# AD8232.net
KiCad netlist of a schematic drawn in Altium Designer
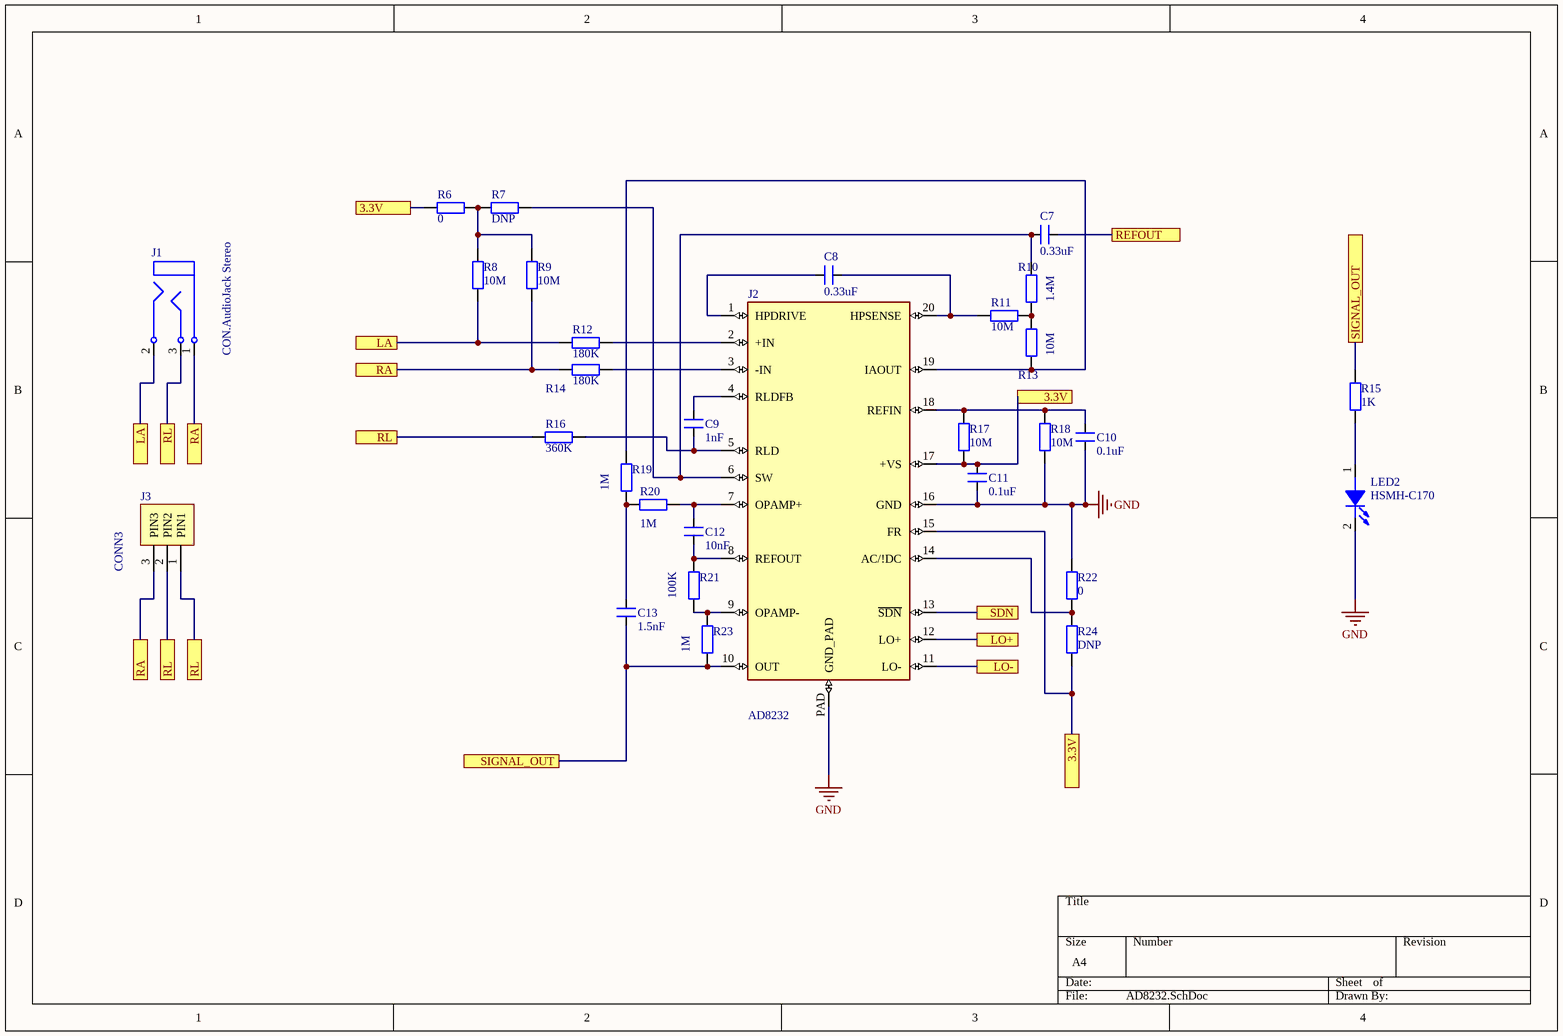
[diagram p0: AD8232.SchDoc]

(export (version "E")
  (design (tool "Eeschema 10.0.6"))
  (components
    (comp (ref "C7")
      (value "0.33uF")
      (footprint "SM-0805")
      (description "Cap SMD")
      (libsource (lib "hphonglib") (part "CM"))
    )
    (comp (ref "C8")
      (value "0.33uF")
      (footprint "SM-0805")
      (description "Cap SMD")
      (libsource (lib "hphonglib") (part "CM"))
    )
    (comp (ref "C9")
      (value "1nF")
      (footprint "SM-0805")
      (description "Cap SMD")
      (libsource (lib "hphonglib") (part "CM"))
    )
    (comp (ref "C10")
      (value "0.1uF")
      (footprint "SM-0805")
      (description "Cap SMD")
      (libsource (lib "hphonglib") (part "CM"))
    )
    (comp (ref "C11")
      (value "0.1uF")
      (footprint "SM-0805")
      (description "Cap SMD")
      (libsource (lib "hphonglib") (part "CM"))
    )
    (comp (ref "C12")
      (value "10nF")
      (footprint "SM-0805")
      (description "Cap SMD")
      (libsource (lib "hphonglib") (part "CM"))
    )
    (comp (ref "C13")
      (value "1.5nF")
      (footprint "SM-0805")
      (description "Cap SMD")
      (libsource (lib "hphonglib") (part "CM"))
    )
    (comp (ref "J1")
      (value "CON.AudioJack Stereo")
      (footprint "SJ-3523-SMT")
      (description "AUDIO JACK 3.5MM STEREO SMD")
      (fields (field (name "PUBLISHER") "Altium Limited"))
      (libsource (lib "hphonglib") (part "CON.AudioJack Stereo"))
    )
    (comp (ref "J2")
      (value "AD8232")
      (footprint "AD8232")
      (description "ECG Front End 20-LFCSP-WQ (4x4)")
      (fields (field (name "MF") "Analog Devices"))
      (libsource (lib "ECG_Taller_2021") (part "AD8232"))
    )
    (comp (ref "J3")
      (value "CONN3")
      (footprint "CONN3")
      (libsource (lib "Schlib-PCB-Invernadero") (part "Bornera_3_pin"))
    )
    (comp (ref "LED2")
      (value "HSMH-C170")
      (footprint "LED.SMD.RED")
      (description "Typical GaAs SMD LED")
      (fields (field (name "MANUFACTURER") "Lite-On Inc") (field (name "PUBLISHER") "Hoang Nguyen"))
      (libsource (lib "hphonglib") (part "LED_1"))
    )
    (comp (ref "R6")
      (value "0")
      (footprint "DIEN TRO 0805")
      (description "RES_0805")
      (fields (field (name "Comment") "RES_SMD_0805") (field (name "PUBLISHER") "Altium Limited"))
      (libsource (lib "") (part "RES_SMD_0805_1"))
    )
    (comp (ref "R7")
      (value "DNP")
      (footprint "DIEN TRO 0805")
      (description "RES_0805")
      (fields (field (name "Comment") "RES_SMD_0805") (field (name "PUBLISHER") "Altium Limited"))
      (libsource (lib "") (part "RES_SMD_0805_1"))
    )
    (comp (ref "R8")
      (value "10M")
      (footprint "DIEN TRO 0805")
      (description "RES_0805")
      (fields (field (name "Comment") "RES_SMD_0805") (field (name "PUBLISHER") "Altium Limited"))
      (libsource (lib "hphonglib") (part "RES_SMD_0805"))
    )
    (comp (ref "R9")
      (value "10M")
      (footprint "DIEN TRO 0805")
      (description "RES_0805")
      (fields (field (name "Comment") "RES_SMD_0805") (field (name "PUBLISHER") "Altium Limited"))
      (libsource (lib "hphonglib") (part "RES_SMD_0805"))
    )
    (comp (ref "R10")
      (value "1.4M")
      (footprint "DIEN TRO 0805")
      (description "RES_0805")
      (fields (field (name "Comment") "RES_SMD_0805") (field (name "PUBLISHER") "Altium Limited"))
      (libsource (lib "hphonglib") (part "RES_SMD_0805"))
    )
    (comp (ref "R11")
      (value "10M")
      (footprint "DIEN TRO 0805")
      (description "RES_0805")
      (fields (field (name "Comment") "RES_SMD_0805") (field (name "PUBLISHER") "Altium Limited"))
      (libsource (lib "") (part "RES_SMD_0805_1"))
    )
    (comp (ref "R12")
      (value "180K")
      (footprint "DIEN TRO 0805")
      (description "RES_0805")
      (fields (field (name "Comment") "RES_SMD_0805") (field (name "PUBLISHER") "Altium Limited"))
      (libsource (lib "") (part "RES_SMD_0805_1"))
    )
    (comp (ref "R13")
      (value "10M")
      (footprint "DIEN TRO 0805")
      (description "RES_0805")
      (fields (field (name "Comment") "RES_SMD_0805") (field (name "PUBLISHER") "Altium Limited"))
      (libsource (lib "hphonglib") (part "RES_SMD_0805"))
    )
    (comp (ref "R14")
      (value "180K")
      (footprint "DIEN TRO 0805")
      (description "RES_0805")
      (fields (field (name "Comment") "RES_SMD_0805") (field (name "PUBLISHER") "Altium Limited"))
      (libsource (lib "") (part "RES_SMD_0805_1"))
    )
    (comp (ref "R15")
      (value "1K")
      (footprint "DIEN TRO 0805")
      (description "RES_0805")
      (fields (field (name "Comment") "RES_SMD_0805") (field (name "PUBLISHER") "Altium Limited"))
      (libsource (lib "") (part "RES_SMD_0805_2"))
    )
    (comp (ref "R16")
      (value "360K")
      (footprint "DIEN TRO 0805")
      (description "RES_0805")
      (fields (field (name "Comment") "RES_SMD_0805") (field (name "PUBLISHER") "Altium Limited"))
      (libsource (lib "") (part "RES_SMD_0805_1"))
    )
    (comp (ref "R17")
      (value "10M")
      (footprint "DIEN TRO 0805")
      (description "RES_0805")
      (fields (field (name "Comment") "RES_SMD_0805") (field (name "PUBLISHER") "Altium Limited"))
      (libsource (lib "hphonglib") (part "RES_SMD_0805"))
    )
    (comp (ref "R18")
      (value "10M")
      (footprint "DIEN TRO 0805")
      (description "RES_0805")
      (fields (field (name "Comment") "RES_SMD_0805") (field (name "PUBLISHER") "Altium Limited"))
      (libsource (lib "hphonglib") (part "RES_SMD_0805"))
    )
    (comp (ref "R19")
      (value "1M")
      (footprint "DIEN TRO 0805")
      (description "RES_0805")
      (fields (field (name "Comment") "RES_SMD_0805") (field (name "PUBLISHER") "Altium Limited"))
      (libsource (lib "hphonglib") (part "RES_SMD_0805"))
    )
    (comp (ref "R20")
      (value "1M")
      (footprint "DIEN TRO 0805")
      (description "RES_0805")
      (fields (field (name "Comment") "RES_SMD_0805") (field (name "PUBLISHER") "Altium Limited"))
      (libsource (lib "") (part "RES_SMD_0805_1"))
    )
    (comp (ref "R21")
      (value "100K")
      (footprint "DIEN TRO 0805")
      (description "RES_0805")
      (fields (field (name "Comment") "RES_SMD_0805") (field (name "PUBLISHER") "Altium Limited"))
      (libsource (lib "hphonglib") (part "RES_SMD_0805"))
    )
    (comp (ref "R22")
      (value "0")
      (footprint "DIEN TRO 0805")
      (description "RES_0805")
      (fields (field (name "Comment") "RES_SMD_0805") (field (name "PUBLISHER") "Altium Limited"))
      (libsource (lib "hphonglib") (part "RES_SMD_0805"))
    )
    (comp (ref "R23")
      (value "1M")
      (footprint "DIEN TRO 0805")
      (description "RES_0805")
      (fields (field (name "Comment") "RES_SMD_0805") (field (name "PUBLISHER") "Altium Limited"))
      (libsource (lib "hphonglib") (part "RES_SMD_0805"))
    )
    (comp (ref "R24")
      (value "DNP")
      (footprint "DIEN TRO 0805")
      (description "RES_0805")
      (fields (field (name "Comment") "RES_SMD_0805") (field (name "PUBLISHER") "Altium Limited"))
      (libsource (lib "hphonglib") (part "RES_SMD_0805"))
    )
  )
  (nets
    (net (code "1") (name "/3.3V") (class "Default")
      (node (ref "C11") (pin "2") (pinfunction "2_2") (pintype "passive"))
      (node (ref "J2") (pin "15") (pinfunction "FR_15") (pintype "bidirectional"))
      (node (ref "J2") (pin "17") (pinfunction "+VS_17") (pintype "bidirectional"))
      (node (ref "R17") (pin "1") (pinfunction "1_1") (pintype "passive"))
      (node (ref "R24") (pin "1") (pinfunction "1_1") (pintype "passive"))
      (node (ref "R6") (pin "1") (pinfunction "1_1") (pintype "passive"))
    )
    (net (code "2") (name "/LA") (class "Default")
      (node (ref "J1") (pin "2") (pinfunction "2_2") (pintype "passive"))
      (node (ref "R12") (pin "1") (pinfunction "1_1") (pintype "passive"))
      (node (ref "R8") (pin "1") (pinfunction "1_1") (pintype "passive"))
    )
    (net (code "3") (name "/LO+") (class "Default")
      (node (ref "J2") (pin "12") (pinfunction "LO+_12") (pintype "bidirectional"))
    )
    (net (code "4") (name "/LO-") (class "Default")
      (node (ref "J2") (pin "11") (pinfunction "LO-_11") (pintype "bidirectional"))
    )
    (net (code "5") (name "/RA") (class "Default")
      (node (ref "J1") (pin "1") (pinfunction "1_1") (pintype "passive"))
      (node (ref "J3") (pin "3") (pinfunction "PIN3_3") (pintype "passive"))
      (node (ref "R14") (pin "1") (pinfunction "1_1") (pintype "passive"))
      (node (ref "R9") (pin "1") (pinfunction "1_1") (pintype "passive"))
    )
    (net (code "6") (name "/REFOUT") (class "Default")
      (node (ref "C7") (pin "2") (pinfunction "2_2") (pintype "passive"))
    )
    (net (code "7") (name "/RL") (class "Default")
      (node (ref "J1") (pin "3") (pinfunction "3_3") (pintype "passive"))
      (node (ref "J3") (pin "1") (pinfunction "PIN1_1") (pintype "passive"))
      (node (ref "J3") (pin "2") (pinfunction "PIN2_2") (pintype "passive"))
      (node (ref "R16") (pin "1") (pinfunction "1_1") (pintype "passive"))
    )
    (net (code "8") (name "/SDN") (class "Default")
      (node (ref "J2") (pin "13") (pinfunction "~{SDN}_13") (pintype "bidirectional"))
    )
    (net (code "9") (name "/SIGNAL_OUT") (class "Default")
      (node (ref "C13") (pin "1") (pinfunction "1_1") (pintype "passive"))
      (node (ref "J2") (pin "10") (pinfunction "OUT_10") (pintype "bidirectional"))
      (node (ref "R15") (pin "1") (pinfunction "1_1") (pintype "passive"))
      (node (ref "R23") (pin "1") (pinfunction "1_1") (pintype "passive"))
    )
    (net (code "10") (name "GND") (class "Default")
      (node (ref "C10") (pin "1") (pinfunction "1_1") (pintype "passive"))
      (node (ref "C11") (pin "1") (pinfunction "1_1") (pintype "passive"))
      (node (ref "J2") (pin "16") (pinfunction "GND_16") (pintype "bidirectional"))
      (node (ref "J2") (pin "PAD") (pinfunction "GND_PAD_PAD") (pintype "bidirectional"))
      (node (ref "LED2") (pin "2") (pinfunction "K_2") (pintype "passive"))
      (node (ref "R18") (pin "1") (pinfunction "1_1") (pintype "passive"))
      (node (ref "R22") (pin "2") (pinfunction "2_2") (pintype "passive"))
    )
    (net (code "11") (name "Net-(C13-Pad2)") (class "Default")
      (node (ref "C13") (pin "2") (pinfunction "2_2") (pintype "passive"))
      (node (ref "R19") (pin "1") (pinfunction "1_1") (pintype "passive"))
      (node (ref "R20") (pin "1") (pinfunction "1_1") (pintype "passive"))
    )
    (net (code "12") (name "Net-(J2-+IN)") (class "Default")
      (node (ref "J2") (pin "2") (pinfunction "+IN_2") (pintype "bidirectional"))
      (node (ref "R12") (pin "2") (pinfunction "2_2") (pintype "passive"))
    )
    (net (code "13") (name "Net-(J2--IN)") (class "Default")
      (node (ref "J2") (pin "3") (pinfunction "-IN_3") (pintype "bidirectional"))
      (node (ref "R14") (pin "2") (pinfunction "2_2") (pintype "passive"))
    )
    (net (code "14") (name "Net-(J2-AC{slash}!DC)") (class "Default")
      (node (ref "J2") (pin "14") (pinfunction "AC/!DC_14") (pintype "bidirectional"))
      (node (ref "R22") (pin "1") (pinfunction "1_1") (pintype "passive"))
      (node (ref "R24") (pin "2") (pinfunction "2_2") (pintype "passive"))
    )
    (net (code "15") (name "Net-(J2-HPDRIVE)") (class "Default")
      (node (ref "C8") (pin "1") (pinfunction "1_1") (pintype "passive"))
      (node (ref "J2") (pin "1") (pinfunction "HPDRIVE_1") (pintype "bidirectional"))
    )
    (net (code "16") (name "Net-(J2-HPSENSE)") (class "Default")
      (node (ref "C8") (pin "2") (pinfunction "2_2") (pintype "passive"))
      (node (ref "J2") (pin "20") (pinfunction "HPSENSE_20") (pintype "bidirectional"))
      (node (ref "R11") (pin "1") (pinfunction "1_1") (pintype "passive"))
    )
    (net (code "17") (name "Net-(J2-IAOUT)") (class "Default")
      (node (ref "J2") (pin "19") (pinfunction "IAOUT_19") (pintype "bidirectional"))
      (node (ref "R13") (pin "1") (pinfunction "1_1") (pintype "passive"))
      (node (ref "R19") (pin "2") (pinfunction "2_2") (pintype "passive"))
    )
    (net (code "18") (name "Net-(J2-OPAMP+)") (class "Default")
      (node (ref "C12") (pin "2") (pinfunction "2_2") (pintype "passive"))
      (node (ref "J2") (pin "7") (pinfunction "OPAMP+_7") (pintype "bidirectional"))
      (node (ref "R20") (pin "2") (pinfunction "2_2") (pintype "passive"))
    )
    (net (code "19") (name "Net-(J2-OPAMP-)") (class "Default")
      (node (ref "J2") (pin "9") (pinfunction "OPAMP-_9") (pintype "bidirectional"))
      (node (ref "R21") (pin "1") (pinfunction "1_1") (pintype "passive"))
      (node (ref "R23") (pin "2") (pinfunction "2_2") (pintype "passive"))
    )
    (net (code "20") (name "Net-(J2-REFIN)") (class "Default")
      (node (ref "C10") (pin "2") (pinfunction "2_2") (pintype "passive"))
      (node (ref "J2") (pin "18") (pinfunction "REFIN_18") (pintype "bidirectional"))
      (node (ref "R17") (pin "2") (pinfunction "2_2") (pintype "passive"))
      (node (ref "R18") (pin "2") (pinfunction "2_2") (pintype "passive"))
    )
    (net (code "21") (name "Net-(J2-REFOUT)") (class "Default")
      (node (ref "C12") (pin "1") (pinfunction "1_1") (pintype "passive"))
      (node (ref "J2") (pin "8") (pinfunction "REFOUT_8") (pintype "bidirectional"))
      (node (ref "R21") (pin "2") (pinfunction "2_2") (pintype "passive"))
    )
    (net (code "22") (name "Net-(J2-RLD)") (class "Default")
      (node (ref "C9") (pin "1") (pinfunction "1_1") (pintype "passive"))
      (node (ref "J2") (pin "5") (pinfunction "RLD_5") (pintype "bidirectional"))
      (node (ref "R16") (pin "2") (pinfunction "2_2") (pintype "passive"))
    )
    (net (code "23") (name "Net-(J2-RLDFB)") (class "Default")
      (node (ref "C9") (pin "2") (pinfunction "2_2") (pintype "passive"))
      (node (ref "J2") (pin "4") (pinfunction "RLDFB_4") (pintype "bidirectional"))
    )
    (net (code "24") (name "Net-(J2-SW)") (class "Default")
      (node (ref "C7") (pin "1") (pinfunction "1_1") (pintype "passive"))
      (node (ref "J2") (pin "6") (pinfunction "SW_6") (pintype "bidirectional"))
      (node (ref "R10") (pin "2") (pinfunction "2_2") (pintype "passive"))
      (node (ref "R7") (pin "2") (pinfunction "2_2") (pintype "passive"))
    )
    (net (code "25") (name "Net-(LED2-A)") (class "Default")
      (node (ref "LED2") (pin "1") (pinfunction "A_1") (pintype "passive"))
      (node (ref "R15") (pin "2") (pinfunction "2_2") (pintype "passive"))
    )
    (net (code "26") (name "Net-(R6-Pad2)") (class "Default")
      (node (ref "R6") (pin "2") (pinfunction "2_2") (pintype "passive"))
      (node (ref "R7") (pin "1") (pinfunction "1_1") (pintype "passive"))
      (node (ref "R8") (pin "2") (pinfunction "2_2") (pintype "passive"))
      (node (ref "R9") (pin "2") (pinfunction "2_2") (pintype "passive"))
    )
    (net (code "27") (name "Net-(R10-Pad1)") (class "Default")
      (node (ref "R10") (pin "1") (pinfunction "1_1") (pintype "passive"))
      (node (ref "R11") (pin "2") (pinfunction "2_2") (pintype "passive"))
      (node (ref "R13") (pin "2") (pinfunction "2_2") (pintype "passive"))
    )
  )
)
